# Power.net
KiCad netlist of a schematic drawn in Altium Designer
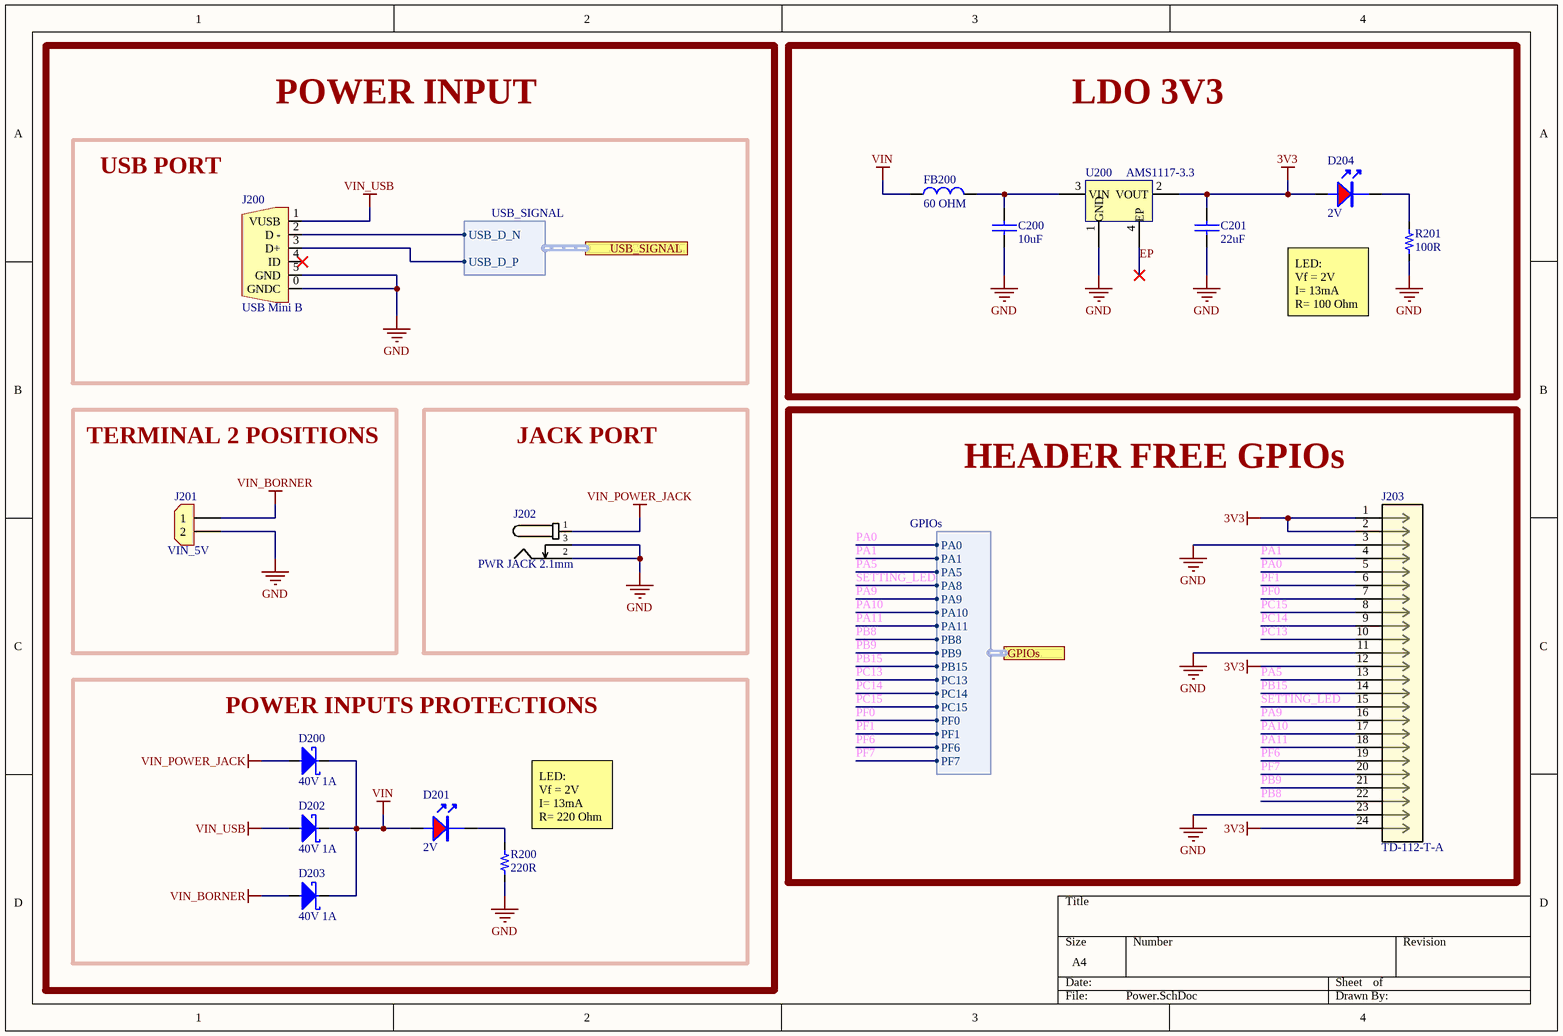
[diagram p0: Power.SchDoc]

(export (version "E")
  (design (tool "Eeschema 10.0.6"))
  (components
    (comp (ref "C200")
      (value "10uF")
      (footprint "0603_cap")
      (description "10V 10uF X5R ±10% 0603 Multilayer Ceramic Capacitors MLCC - SMD/SMT ROHS")
      (fields
        (field (name "MANUFACTURER") "CCTC")
        (field (name "MANUFACTURER PART NUMBER") "TCC0603X5R106K100CT")
      )
      (libsource (lib "shared_lib") (part "Cap_10uF_0603_10V"))
    )
    (comp (ref "C201")
      (value "22uF")
      (footprint "0603_cap")
      (description "6.3V 22uF X5R ±20% 0805 Multilayer Ceramic Capacitors MLCC - SMD/SMT ROHS")
      (fields
        (field (name "MANUFACTURER") "Samsung Electro-Mechanics")
        (field (name "MANUFACTURER PART NUMBER") "CL21A226MQQNNNE")
      )
      (libsource (lib "shared_lib") (part "Cap_22uF_0805_6V3"))
    )
    (comp (ref "D200")
      (value "40V 1A")
      (footprint "SOD_123")
      (description "DIODE SCHOTTKY 40V 1A SOD123F")
      (fields
        (field (name "MANUFACTURER") "Shanghai Prisemi Elec")
        (field (name "MANUFACTURER PART NUMBER") "PSBD1DF40V1H")
      )
      (libsource (lib "shared_lib") (part "D_Schottky_40V_1A_SOD_123F"))
    )
    (comp (ref "D201")
      (value "2V")
      (footprint "0805_LED")
      (description "LED RED CLEAR 0805 SMD")
      (fields
        (field (name "MANUFACTURER") "XINGLIGHT")
        (field (name "MANUFACTURER PART NUMBER") "XL-2012SURC")
      )
      (libsource (lib "shared_lib") (part "LED_0805_RED"))
    )
    (comp (ref "D202")
      (value "40V 1A")
      (footprint "SOD_123")
      (description "DIODE SCHOTTKY 40V 1A SOD123F")
      (fields
        (field (name "MANUFACTURER") "Shanghai Prisemi Elec")
        (field (name "MANUFACTURER PART NUMBER") "PSBD1DF40V1H")
      )
      (libsource (lib "shared_lib") (part "D_Schottky_40V_1A_SOD_123F"))
    )
    (comp (ref "D203")
      (value "40V 1A")
      (footprint "SOD_123")
      (description "DIODE SCHOTTKY 40V 1A SOD123F")
      (fields
        (field (name "MANUFACTURER") "Shanghai Prisemi Elec")
        (field (name "MANUFACTURER PART NUMBER") "PSBD1DF40V1H")
      )
      (libsource (lib "shared_lib") (part "D_Schottky_40V_1A_SOD_123F"))
    )
    (comp (ref "D204")
      (value "2V")
      (footprint "0805_LED")
      (description "LED RED CLEAR 0805 SMD")
      (fields
        (field (name "MANUFACTURER") "XINGLIGHT")
        (field (name "MANUFACTURER PART NUMBER") "XL-2012SURC")
      )
      (libsource (lib "shared_lib") (part "LED_0805_RED"))
    )
    (comp (ref "FB200")
      (value "60 OHM")
      (footprint "0603_fb")
      (description "2A 1 100mΩ 60Ω@100MHz ±25% 0603 Ferrite Beads ROHS")
      (fields
        (field (name "MANUFACTURER") "TAI-TECH")
        (field (name "MANUFACTURER PART NUMBER") "HCB1608KF-600T20")
      )
      (libsource (lib "shared_lib") (part "FB_60_0603_2A"))
    )
    (comp (ref "J200")
      (value "USB Mini B")
      (footprint "CON_5x1_SMD_miniUSB_B")
      (description "CONN RCPT USB2.0 MINI B SMD R/A")
      (fields
        (field (name "MANUFACTURER PART NUMBER") "KH-MINI-SMT-5P-Cu")
        (field (name "MANUFACTURER") "EDAC Inc.")
      )
      (libsource (lib "shared_lib") (part "Con_Mini_USB_B"))
    )
    (comp (ref "J201")
      (value "VIN_5V")
      (footprint "CON_2x1_TH_5MM")
      (description "2POS 5MM")
      (fields (field (name "MANUFACTURER") "JILN") (field (name "MANUFACTURER PART NUMBER") "JL126-50002G01"))
      (libsource (lib "shared_lib") (part "Con_2x1_TH_5mm"))
    )
    (comp (ref "J202")
      (value "PWR JACK 2.1mm")
      (footprint "CON_POWER_BARREL_2.1MM_3CONN")
      (description "CONN PWR JACK 2X5.5MM SOLDER")
      (fields (field (name "MANUFACTURER") "HCTL") (field (name "MANUFACTURER PART NUMBER") "HC-DC-005-2.0T"))
      (libsource (lib "shared_lib") (part "Con_Power_Jack_2.1mm_3pins"))
    )
    (comp (ref "J203")
      (value "TD-112-T-A")
      (footprint "CON_12X2_TH_2.54mm")
      (description "CONN HEADER VERT 24POS 2.54MM")
      (fields (field (name "MANUFACTURER") "Samtec Inc."))
      (libsource (lib "shared_lib") (part "Con_12X2_TH_2.54mm"))
    )
    (comp (ref "R200")
      (value "220R")
      (footprint "0603_res")
      (description "RES SMD 220R OHM 5% 1/10W 0603")
      (fields
        (field (name "MANUFACTURER") "FOJAN")
        (field (name "MANUFACTURER PART NUMBER") "FRC0603J221 TS")
      )
      (libsource (lib "shared_lib") (part "Res_220R_0603_1/10W"))
    )
    (comp (ref "R201")
      (value "100R")
      (footprint "0603_res")
      (description "RES SMD 100R OHM 5% 1/10W 0603")
      (fields
        (field (name "MANUFACTURER") "FOJAN")
        (field (name "MANUFACTURER PART NUMBER") "FRC0603J101 TS")
      )
      (libsource (lib "shared_lib") (part "Res_100R_0603_1/10W"))
    )
    (comp (ref "U200")
      (value "AMS1117-3.3")
      (footprint "SOT_223")
      (description "1A 60dB@(120Hz) Fixed 3.3V Positive 18V SOT-223 Linear Voltage Regulators (LDO) ROHS")
      (fields (field (name "MANUFACTURER") "UMW(Youtai Semiconductor Co., Ltd.)"))
      (libsource (lib "shared_lib") (part "LDO_3V3_1A_FIXED"))
    )
  )
  (nets
    (net (code "3") (name "/EP") (class "Default")
      (node (ref "U200") (pin "4") (pinfunction "EP_4") (pintype "passive+no_connect"))
    )
    (net (code "4") (name "/PA0") (class "Default")
      (node (ref "J203") (pin "5") (pinfunction "5_5") (pintype "passive"))
    )
    (net (code "5") (name "/PA1") (class "Default")
      (node (ref "J203") (pin "4") (pinfunction "4_4") (pintype "passive"))
    )
    (net (code "6") (name "/PA5") (class "Default")
      (node (ref "J203") (pin "13") (pinfunction "13_13") (pintype "passive"))
    )
    (net (code "7") (name "/PA9") (class "Default")
      (node (ref "J203") (pin "16") (pinfunction "16_16") (pintype "passive"))
    )
    (net (code "8") (name "/PA10") (class "Default")
      (node (ref "J203") (pin "17") (pinfunction "17_17") (pintype "passive"))
    )
    (net (code "9") (name "/PA11") (class "Default")
      (node (ref "J203") (pin "18") (pinfunction "18_18") (pintype "passive"))
    )
    (net (code "10") (name "/PB8") (class "Default")
      (node (ref "J203") (pin "22") (pinfunction "22_22") (pintype "passive"))
    )
    (net (code "11") (name "/PB9") (class "Default")
      (node (ref "J203") (pin "21") (pinfunction "21_21") (pintype "passive"))
    )
    (net (code "12") (name "/PB15") (class "Default")
      (node (ref "J203") (pin "14") (pinfunction "14_14") (pintype "passive"))
    )
    (net (code "13") (name "/PC13") (class "Default")
      (node (ref "J203") (pin "10") (pinfunction "10_10") (pintype "passive"))
    )
    (net (code "14") (name "/PC14") (class "Default")
      (node (ref "J203") (pin "9") (pinfunction "9_9") (pintype "passive"))
    )
    (net (code "15") (name "/PC15") (class "Default")
      (node (ref "J203") (pin "8") (pinfunction "8_8") (pintype "passive"))
    )
    (net (code "16") (name "/PF0") (class "Default")
      (node (ref "J203") (pin "7") (pinfunction "7_7") (pintype "passive"))
    )
    (net (code "17") (name "/PF1") (class "Default")
      (node (ref "J203") (pin "6") (pinfunction "6_6") (pintype "passive"))
    )
    (net (code "18") (name "/PF6") (class "Default")
      (node (ref "J203") (pin "19") (pinfunction "19_19") (pintype "passive"))
    )
    (net (code "19") (name "/PF7") (class "Default")
      (node (ref "J203") (pin "20") (pinfunction "20_20") (pintype "passive"))
    )
    (net (code "20") (name "/SETTING_LED") (class "Default")
      (node (ref "J203") (pin "15") (pinfunction "15_15") (pintype "passive"))
    )
    (net (code "21") (name "/USB_D_N") (class "Default")
      (node (ref "J200") (pin "2") (pinfunction "D_-_2") (pintype "passive"))
    )
    (net (code "22") (name "/USB_D_P") (class "Default")
      (node (ref "J200") (pin "3") (pinfunction "D+_3") (pintype "passive"))
    )
    (net (code "25") (name "3V3") (class "Default")
      (node (ref "C201") (pin "1") (pinfunction "1_1") (pintype "passive"))
      (node (ref "D204") (pin "1") (pinfunction "A_1") (pintype "passive"))
      (node (ref "J203") (pin "1") (pinfunction "1_1") (pintype "passive"))
      (node (ref "J203") (pin "12") (pinfunction "12_12") (pintype "passive"))
      (node (ref "J203") (pin "2") (pinfunction "2_2") (pintype "passive"))
      (node (ref "J203") (pin "24") (pinfunction "24_24") (pintype "passive"))
      (node (ref "U200") (pin "2") (pinfunction "VOUT_2") (pintype "passive"))
    )
    (net (code "26") (name "GND") (class "Default")
      (node (ref "C200") (pin "2") (pinfunction "2_2") (pintype "passive"))
      (node (ref "C201") (pin "2") (pinfunction "2_2") (pintype "passive"))
      (node (ref "J200") (pin "0") (pinfunction "GNDC_0") (pintype "passive"))
      (node (ref "J200") (pin "5") (pinfunction "GND_5") (pintype "passive"))
      (node (ref "J201") (pin "2") (pinfunction "2_2") (pintype "passive"))
      (node (ref "J202") (pin "2") (pinfunction "2_2") (pintype "passive"))
      (node (ref "J202") (pin "3") (pinfunction "3_3") (pintype "passive"))
      (node (ref "J203") (pin "11") (pinfunction "11_11") (pintype "passive"))
      (node (ref "J203") (pin "23") (pinfunction "23_23") (pintype "passive"))
      (node (ref "J203") (pin "3") (pinfunction "3_3") (pintype "passive"))
      (node (ref "R200") (pin "1") (pinfunction "1_1") (pintype "passive"))
      (node (ref "R201") (pin "1") (pinfunction "1_1") (pintype "passive"))
      (node (ref "U200") (pin "1") (pinfunction "GND_1") (pintype "passive"))
    )
    (net (code "27") (name "Net-(D201-Pad2)") (class "Default")
      (node (ref "D201") (pin "2") (pinfunction "2_2") (pintype "passive"))
      (node (ref "R200") (pin "2") (pinfunction "2_2") (pintype "passive"))
    )
    (net (code "28") (name "Net-(D204-Pad2)") (class "Default")
      (node (ref "D204") (pin "2") (pinfunction "2_2") (pintype "passive"))
      (node (ref "R201") (pin "2") (pinfunction "2_2") (pintype "passive"))
    )
    (net (code "29") (name "Net-(U200-VIN)") (class "Default")
      (node (ref "C200") (pin "1") (pinfunction "1_1") (pintype "passive"))
      (node (ref "FB200") (pin "2") (pinfunction "2_2") (pintype "passive"))
      (node (ref "U200") (pin "3") (pinfunction "VIN_3") (pintype "passive"))
    )
    (net (code "30") (name "VIN") (class "Default")
      (node (ref "D200") (pin "1") (pinfunction "1_1") (pintype "passive"))
      (node (ref "D201") (pin "1") (pinfunction "A_1") (pintype "passive"))
      (node (ref "D202") (pin "1") (pinfunction "1_1") (pintype "passive"))
      (node (ref "D203") (pin "1") (pinfunction "1_1") (pintype "passive"))
      (node (ref "FB200") (pin "1") (pinfunction "1_1") (pintype "passive"))
    )
    (net (code "31") (name "VIN_BORNER") (class "Default")
      (node (ref "D203") (pin "2") (pinfunction "2_2") (pintype "passive"))
      (node (ref "J201") (pin "1") (pinfunction "1_1") (pintype "passive"))
    )
    (net (code "32") (name "VIN_POWER_JACK") (class "Default")
      (node (ref "D200") (pin "2") (pinfunction "2_2") (pintype "passive"))
      (node (ref "J202") (pin "1") (pinfunction "1_1") (pintype "passive"))
    )
    (net (code "33") (name "VIN_USB") (class "Default")
      (node (ref "D202") (pin "2") (pinfunction "2_2") (pintype "passive"))
      (node (ref "J200") (pin "1") (pinfunction "VUSB_1") (pintype "passive"))
    )
    (net (code "34") (name "unconnected-(J200-ID-Pad4)") (class "Default")
      (node (ref "J200") (pin "4") (pinfunction "ID_4") (pintype "passive+no_connect"))
    )
  )
)
